# ESP-programmer-2.net
KiCad netlist of a schematic drawn in EAGLE
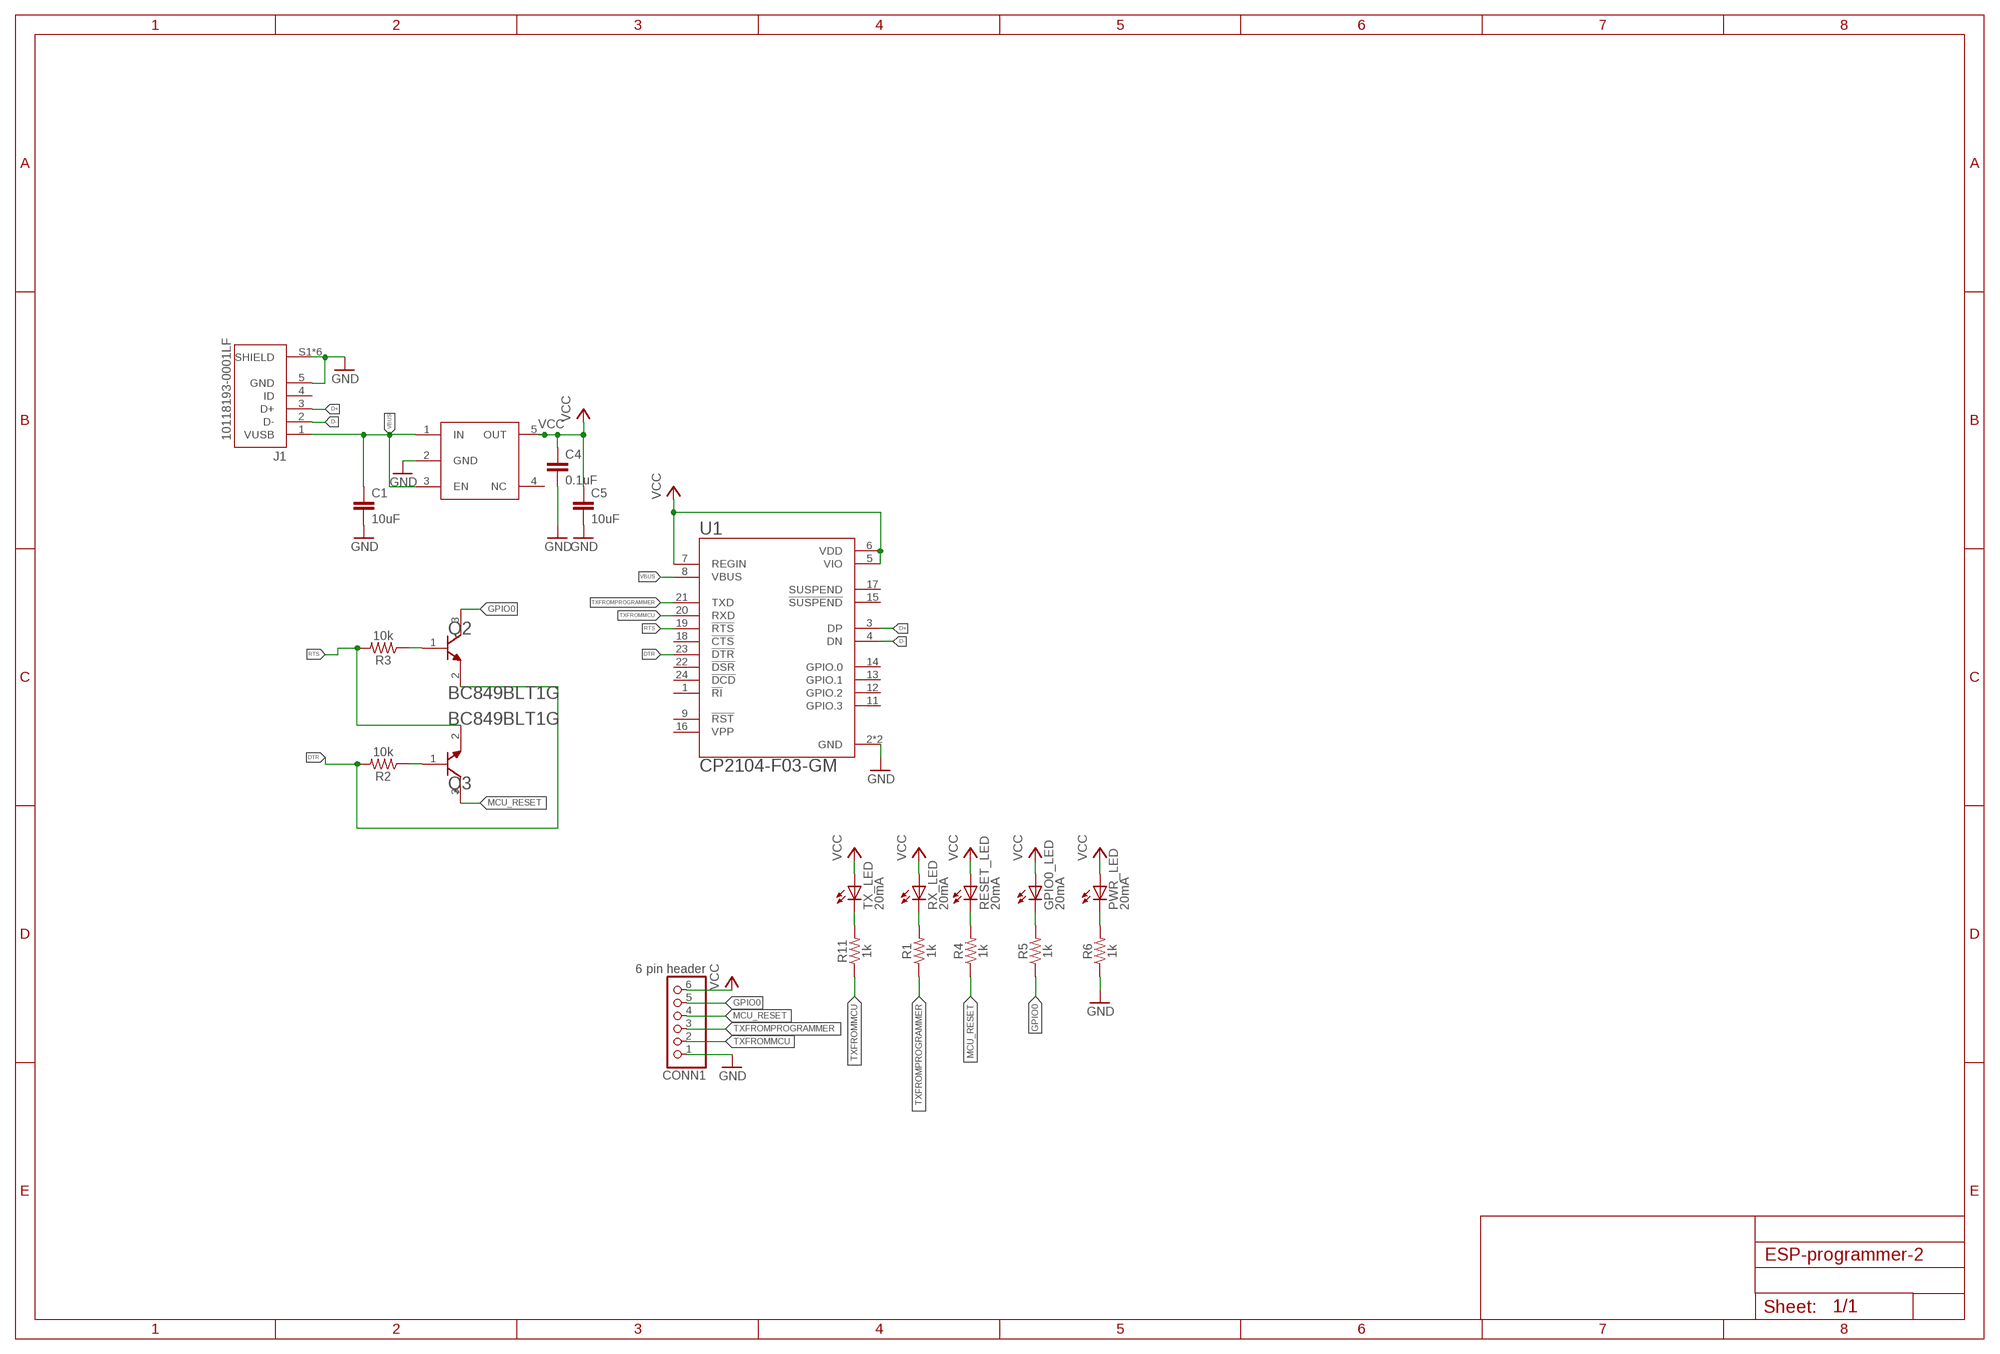
[diagram p0: schematic, sheet 1]

(export (version "E")
  (design (tool "Eeschema 10.0.6"))
  (components
    (comp (ref "C1")
      (value "10uF")
      (footprint "eagle-import:C0603")
      (libsource (lib "eagle-import") (part "C-EUC0603"))
    )
    (comp (ref "C4")
      (value "0.1uF")
      (footprint "eagle-import:C0603")
      (libsource (lib "eagle-import") (part "C-EUC0603"))
    )
    (comp (ref "C5")
      (value "10uF")
      (footprint "eagle-import:C0603")
      (libsource (lib "eagle-import") (part "C-EUC0603"))
    )
    (comp (ref "CONN1")
      (value "6 pin header")
      (footprint "eagle-import:1X06")
      (libsource (lib "eagle-import") (part "PINHD-1X6"))
    )
    (comp (ref "GPIO0_LED")
      (value "20mA")
      (footprint "eagle-import:CHIP-LED0603")
      (libsource (lib "eagle-import") (part "LEDCHIP-LED0603"))
    )
    (comp (ref "J1")
      (value "10118193-0001LF")
      (footprint "eagle-import:FCI_10118193-0001LF")
      (fields (field (name "MF") "Amphenol FCI"))
      (libsource (lib "eagle-import") (part "10118193-0001LF"))
    )
    (comp (ref "PWR_LED")
      (value "20mA")
      (footprint "eagle-import:CHIP-LED0603")
      (libsource (lib "eagle-import") (part "LEDCHIP-LED0603"))
    )
    (comp (ref "Q2")
      (value "ON_SEMICONDUCTOR_BC849BLT1GON_SEMICONDUCTOR_BC849BLT1G_0_0")
      (footprint "eagle-import:ON_SEMICONDUCTOR_BC849BLT1G_0")
      (fields (field (name "MF") "On Semiconductor") (field (name "MPN") "BC849BLT1G"))
      (libsource (lib "eagle-import") (part "ON_SEMICONDUCTOR_BC849BLT1GON_SEMICONDUCTOR_BC849BLT1G_0_0"))
    )
    (comp (ref "Q3")
      (value "ON_SEMICONDUCTOR_BC849BLT1GON_SEMICONDUCTOR_BC849BLT1G_0_0")
      (footprint "eagle-import:ON_SEMICONDUCTOR_BC849BLT1G_0")
      (fields (field (name "MF") "On Semiconductor") (field (name "MPN") "BC849BLT1G"))
      (libsource (lib "eagle-import") (part "ON_SEMICONDUCTOR_BC849BLT1GON_SEMICONDUCTOR_BC849BLT1G_0_0"))
    )
    (comp (ref "R1")
      (value "1k")
      (footprint "eagle-import:0603")
      (libsource (lib "eagle-import") (part "10KOHM-0603-1/10W-1%"))
    )
    (comp (ref "R2")
      (value "10k")
      (footprint "eagle-import:0603")
      (libsource (lib "eagle-import") (part "10KOHM-0603-1/10W-1%"))
    )
    (comp (ref "R3")
      (value "10k")
      (footprint "eagle-import:0603")
      (libsource (lib "eagle-import") (part "10KOHM-0603-1/10W-1%"))
    )
    (comp (ref "R4")
      (value "1k")
      (footprint "eagle-import:0603")
      (libsource (lib "eagle-import") (part "10KOHM-0603-1/10W-1%"))
    )
    (comp (ref "R5")
      (value "1k")
      (footprint "eagle-import:0603")
      (libsource (lib "eagle-import") (part "10KOHM-0603-1/10W-1%"))
    )
    (comp (ref "R6")
      (value "1k")
      (footprint "eagle-import:0603")
      (libsource (lib "eagle-import") (part "10KOHM-0603-1/10W-1%"))
    )
    (comp (ref "R11")
      (value "1k")
      (footprint "eagle-import:0603")
      (libsource (lib "eagle-import") (part "10KOHM-0603-1/10W-1%"))
    )
    (comp (ref "REG")
      (value "3v3 LDO")
      (footprint "eagle-import:NCP718BSN330T1G")
      (libsource (lib "eagle-import") (part "NCP718BSN330T1G"))
    )
    (comp (ref "RESET_LED")
      (value "20mA")
      (footprint "eagle-import:CHIP-LED0603")
      (libsource (lib "eagle-import") (part "LEDCHIP-LED0603"))
    )
    (comp (ref "RX_LED")
      (value "20mA")
      (footprint "eagle-import:CHIP-LED0603")
      (libsource (lib "eagle-import") (part "LEDCHIP-LED0603"))
    )
    (comp (ref "TX_LED")
      (value "20mA")
      (footprint "eagle-import:CHIP-LED0603")
      (libsource (lib "eagle-import") (part "LEDCHIP-LED0603"))
    )
    (comp (ref "U1")
      (value "CP2104-F03-GM")
      (footprint "eagle-import:QFN50P400X400X80-25N")
      (fields (field (name "MF") "Silicon Labs") (field (name "MP") "CP2104"))
      (libsource (lib "eagle-import") (part "CP2104-F03-GM"))
    )
  )
  (nets
    (net (code "1") (name "D+") (class "Default")
      (node (ref "J1") (pin "3") (pinfunction "D+_3") (pintype "passive"))
      (node (ref "U1") (pin "3") (pinfunction "DP_3") (pintype "bidirectional"))
    )
    (net (code "2") (name "D-") (class "Default")
      (node (ref "J1") (pin "2") (pinfunction "D-_2") (pintype "passive"))
      (node (ref "U1") (pin "4") (pinfunction "DN_4") (pintype "bidirectional"))
    )
    (net (code "3") (name "DTR") (class "Default")
      (node (ref "Q2") (pin "2") (pinfunction "E_2") (pintype "passive"))
      (node (ref "R2") (pin "2") (pinfunction "2_2") (pintype "passive"))
      (node (ref "U1") (pin "23") (pinfunction "~{DTR}_23") (pintype "output"))
    )
    (net (code "4") (name "GND") (class "Default")
      (node (ref "C1") (pin "2") (pinfunction "2_2") (pintype "passive"))
      (node (ref "C4") (pin "2") (pinfunction "2_2") (pintype "passive"))
      (node (ref "C5") (pin "2") (pinfunction "2_2") (pintype "passive"))
      (node (ref "CONN1") (pin "1") (pinfunction "1_1") (pintype "passive"))
      (node (ref "J1") (pin "5") (pinfunction "GND_5") (pintype "passive"))
      (node (ref "J1") (pin "S1") (pinfunction "SHIELD_S1") (pintype "passive"))
      (node (ref "J1") (pin "S2") (pinfunction "SHIELD_S2") (pintype "passive"))
      (node (ref "J1") (pin "S3") (pinfunction "SHIELD_S3") (pintype "passive"))
      (node (ref "J1") (pin "S4") (pinfunction "SHIELD_S4") (pintype "passive"))
      (node (ref "J1") (pin "S5") (pinfunction "SHIELD_S5") (pintype "passive"))
      (node (ref "J1") (pin "S6") (pinfunction "SHIELD_S6") (pintype "passive"))
      (node (ref "R6") (pin "1") (pinfunction "1_1") (pintype "passive"))
      (node (ref "REG") (pin "2") (pinfunction "GND_2") (pintype "power_in"))
      (node (ref "U1") (pin "2") (pinfunction "GND_2") (pintype "power_in"))
      (node (ref "U1") (pin "25") (pinfunction "GND_25") (pintype "power_in"))
    )
    (net (code "5") (name "GPIO0") (class "Default")
      (node (ref "CONN1") (pin "5") (pinfunction "5_5") (pintype "passive"))
      (node (ref "Q2") (pin "3") (pinfunction "C_3") (pintype "passive"))
      (node (ref "R5") (pin "1") (pinfunction "1_1") (pintype "passive"))
    )
    (net (code "6") (name "MCU_RESET") (class "Default")
      (node (ref "CONN1") (pin "4") (pinfunction "4_4") (pintype "passive"))
      (node (ref "Q3") (pin "3") (pinfunction "C_3") (pintype "passive"))
      (node (ref "R4") (pin "1") (pinfunction "1_1") (pintype "passive"))
    )
    (net (code "7") (name "Net-(GPIO0_LED-PadC)") (class "Default")
      (node (ref "GPIO0_LED") (pin "C") (pinfunction "C_C") (pintype "passive"))
      (node (ref "R5") (pin "2") (pinfunction "2_2") (pintype "passive"))
    )
    (net (code "8") (name "Net-(PWR_LED-PadC)") (class "Default")
      (node (ref "PWR_LED") (pin "C") (pinfunction "C_C") (pintype "passive"))
      (node (ref "R6") (pin "2") (pinfunction "2_2") (pintype "passive"))
    )
    (net (code "9") (name "Net-(Q2-B)") (class "Default")
      (node (ref "Q2") (pin "1") (pinfunction "B_1") (pintype "passive"))
      (node (ref "R3") (pin "1") (pinfunction "1_1") (pintype "passive"))
    )
    (net (code "10") (name "Net-(Q3-B)") (class "Default")
      (node (ref "Q3") (pin "1") (pinfunction "B_1") (pintype "passive"))
      (node (ref "R2") (pin "1") (pinfunction "1_1") (pintype "passive"))
    )
    (net (code "11") (name "Net-(R1-Pad2)") (class "Default")
      (node (ref "R1") (pin "2") (pinfunction "2_2") (pintype "passive"))
      (node (ref "RX_LED") (pin "C") (pinfunction "C_C") (pintype "passive"))
    )
    (net (code "12") (name "Net-(R4-Pad2)") (class "Default")
      (node (ref "R4") (pin "2") (pinfunction "2_2") (pintype "passive"))
      (node (ref "RESET_LED") (pin "C") (pinfunction "C_C") (pintype "passive"))
    )
    (net (code "13") (name "Net-(R11-Pad2)") (class "Default")
      (node (ref "R11") (pin "2") (pinfunction "2_2") (pintype "passive"))
      (node (ref "TX_LED") (pin "C") (pinfunction "C_C") (pintype "passive"))
    )
    (net (code "14") (name "RTS") (class "Default")
      (node (ref "Q3") (pin "2") (pinfunction "E_2") (pintype "passive"))
      (node (ref "R3") (pin "2") (pinfunction "2_2") (pintype "passive"))
      (node (ref "U1") (pin "19") (pinfunction "~{RTS}_19") (pintype "output"))
    )
    (net (code "15") (name "TXFROMMCU") (class "Default")
      (node (ref "CONN1") (pin "2") (pinfunction "2_2") (pintype "passive"))
      (node (ref "R11") (pin "1") (pinfunction "1_1") (pintype "passive"))
      (node (ref "U1") (pin "20") (pinfunction "RXD_20") (pintype "input"))
    )
    (net (code "16") (name "TXFROMPROGRAMMER") (class "Default")
      (node (ref "CONN1") (pin "3") (pinfunction "3_3") (pintype "passive"))
      (node (ref "R1") (pin "1") (pinfunction "1_1") (pintype "passive"))
      (node (ref "U1") (pin "21") (pinfunction "TXD_21") (pintype "output"))
    )
    (net (code "17") (name "VBUS") (class "Default")
      (node (ref "C1") (pin "1") (pinfunction "1_1") (pintype "passive"))
      (node (ref "J1") (pin "1") (pinfunction "VUSB_1") (pintype "passive"))
      (node (ref "REG") (pin "1") (pinfunction "IN_1") (pintype "power_in"))
      (node (ref "REG") (pin "3") (pinfunction "EN_3") (pintype "input"))
      (node (ref "U1") (pin "8") (pinfunction "VBUS_8") (pintype "input"))
    )
    (net (code "18") (name "VCC") (class "Default")
      (node (ref "C4") (pin "1") (pinfunction "1_1") (pintype "passive"))
      (node (ref "C5") (pin "1") (pinfunction "1_1") (pintype "passive"))
      (node (ref "CONN1") (pin "6") (pinfunction "6_6") (pintype "passive"))
      (node (ref "GPIO0_LED") (pin "A") (pinfunction "A_A") (pintype "passive"))
      (node (ref "PWR_LED") (pin "A") (pinfunction "A_A") (pintype "passive"))
      (node (ref "REG") (pin "5") (pinfunction "OUT_5") (pintype "power_in"))
      (node (ref "RESET_LED") (pin "A") (pinfunction "A_A") (pintype "passive"))
      (node (ref "RX_LED") (pin "A") (pinfunction "A_A") (pintype "passive"))
      (node (ref "TX_LED") (pin "A") (pinfunction "A_A") (pintype "passive"))
      (node (ref "U1") (pin "5") (pinfunction "VIO_5") (pintype "power_in"))
      (node (ref "U1") (pin "6") (pinfunction "VDD_6") (pintype "power_in"))
      (node (ref "U1") (pin "7") (pinfunction "REGIN_7") (pintype "input"))
    )
    (net (code "19") (name "unconnected-(J1-ID-Pad4)") (class "Default")
      (node (ref "J1") (pin "4") (pinfunction "ID_4") (pintype "passive"))
    )
    (net (code "20") (name "unconnected-(REG-NC-Pad4)") (class "Default")
      (node (ref "REG") (pin "4") (pinfunction "NC_4") (pintype "no_connect"))
    )
    (net (code "21") (name "unconnected-(U1-GPIO.0-Pad14)") (class "Default")
      (node (ref "U1") (pin "14") (pinfunction "GPIO.0_14") (pintype "bidirectional"))
    )
    (net (code "22") (name "unconnected-(U1-GPIO.1-Pad13)") (class "Default")
      (node (ref "U1") (pin "13") (pinfunction "GPIO.1_13") (pintype "bidirectional"))
    )
    (net (code "23") (name "unconnected-(U1-GPIO.2-Pad12)") (class "Default")
      (node (ref "U1") (pin "12") (pinfunction "GPIO.2_12") (pintype "bidirectional"))
    )
    (net (code "24") (name "unconnected-(U1-GPIO.3-Pad11)") (class "Default")
      (node (ref "U1") (pin "11") (pinfunction "GPIO.3_11") (pintype "bidirectional"))
    )
    (net (code "25") (name "unconnected-(U1-SUSPEND-Pad17)") (class "Default")
      (node (ref "U1") (pin "17") (pinfunction "SUSPEND_17") (pintype "output"))
    )
    (net (code "26") (name "unconnected-(U1-VPP-Pad16)") (class "Default")
      (node (ref "U1") (pin "16") (pinfunction "VPP_16") (pintype "passive"))
    )
    (net (code "27") (name "unconnected-(U1-~{CTS}-Pad18)") (class "Default")
      (node (ref "U1") (pin "18") (pinfunction "~{CTS}_18") (pintype "input"))
    )
    (net (code "28") (name "unconnected-(U1-~{DCD}-Pad24)") (class "Default")
      (node (ref "U1") (pin "24") (pinfunction "~{DCD}_24") (pintype "input"))
    )
    (net (code "29") (name "unconnected-(U1-~{DSR}-Pad22)") (class "Default")
      (node (ref "U1") (pin "22") (pinfunction "~{DSR}_22") (pintype "input"))
    )
    (net (code "30") (name "unconnected-(U1-~{RI}-Pad1)") (class "Default")
      (node (ref "U1") (pin "1") (pinfunction "~{RI}_1") (pintype "input"))
    )
    (net (code "31") (name "unconnected-(U1-~{RST}-Pad9)") (class "Default")
      (node (ref "U1") (pin "9") (pinfunction "~{RST}_9") (pintype "bidirectional"))
    )
    (net (code "32") (name "unconnected-(U1-~{SUSPEND}-Pad15)") (class "Default")
      (node (ref "U1") (pin "15") (pinfunction "~{SUSPEND}_15") (pintype "output"))
    )
  )
)
